# Flodar_Board_V1-2.net
KiCad netlist of a schematic drawn in EAGLE
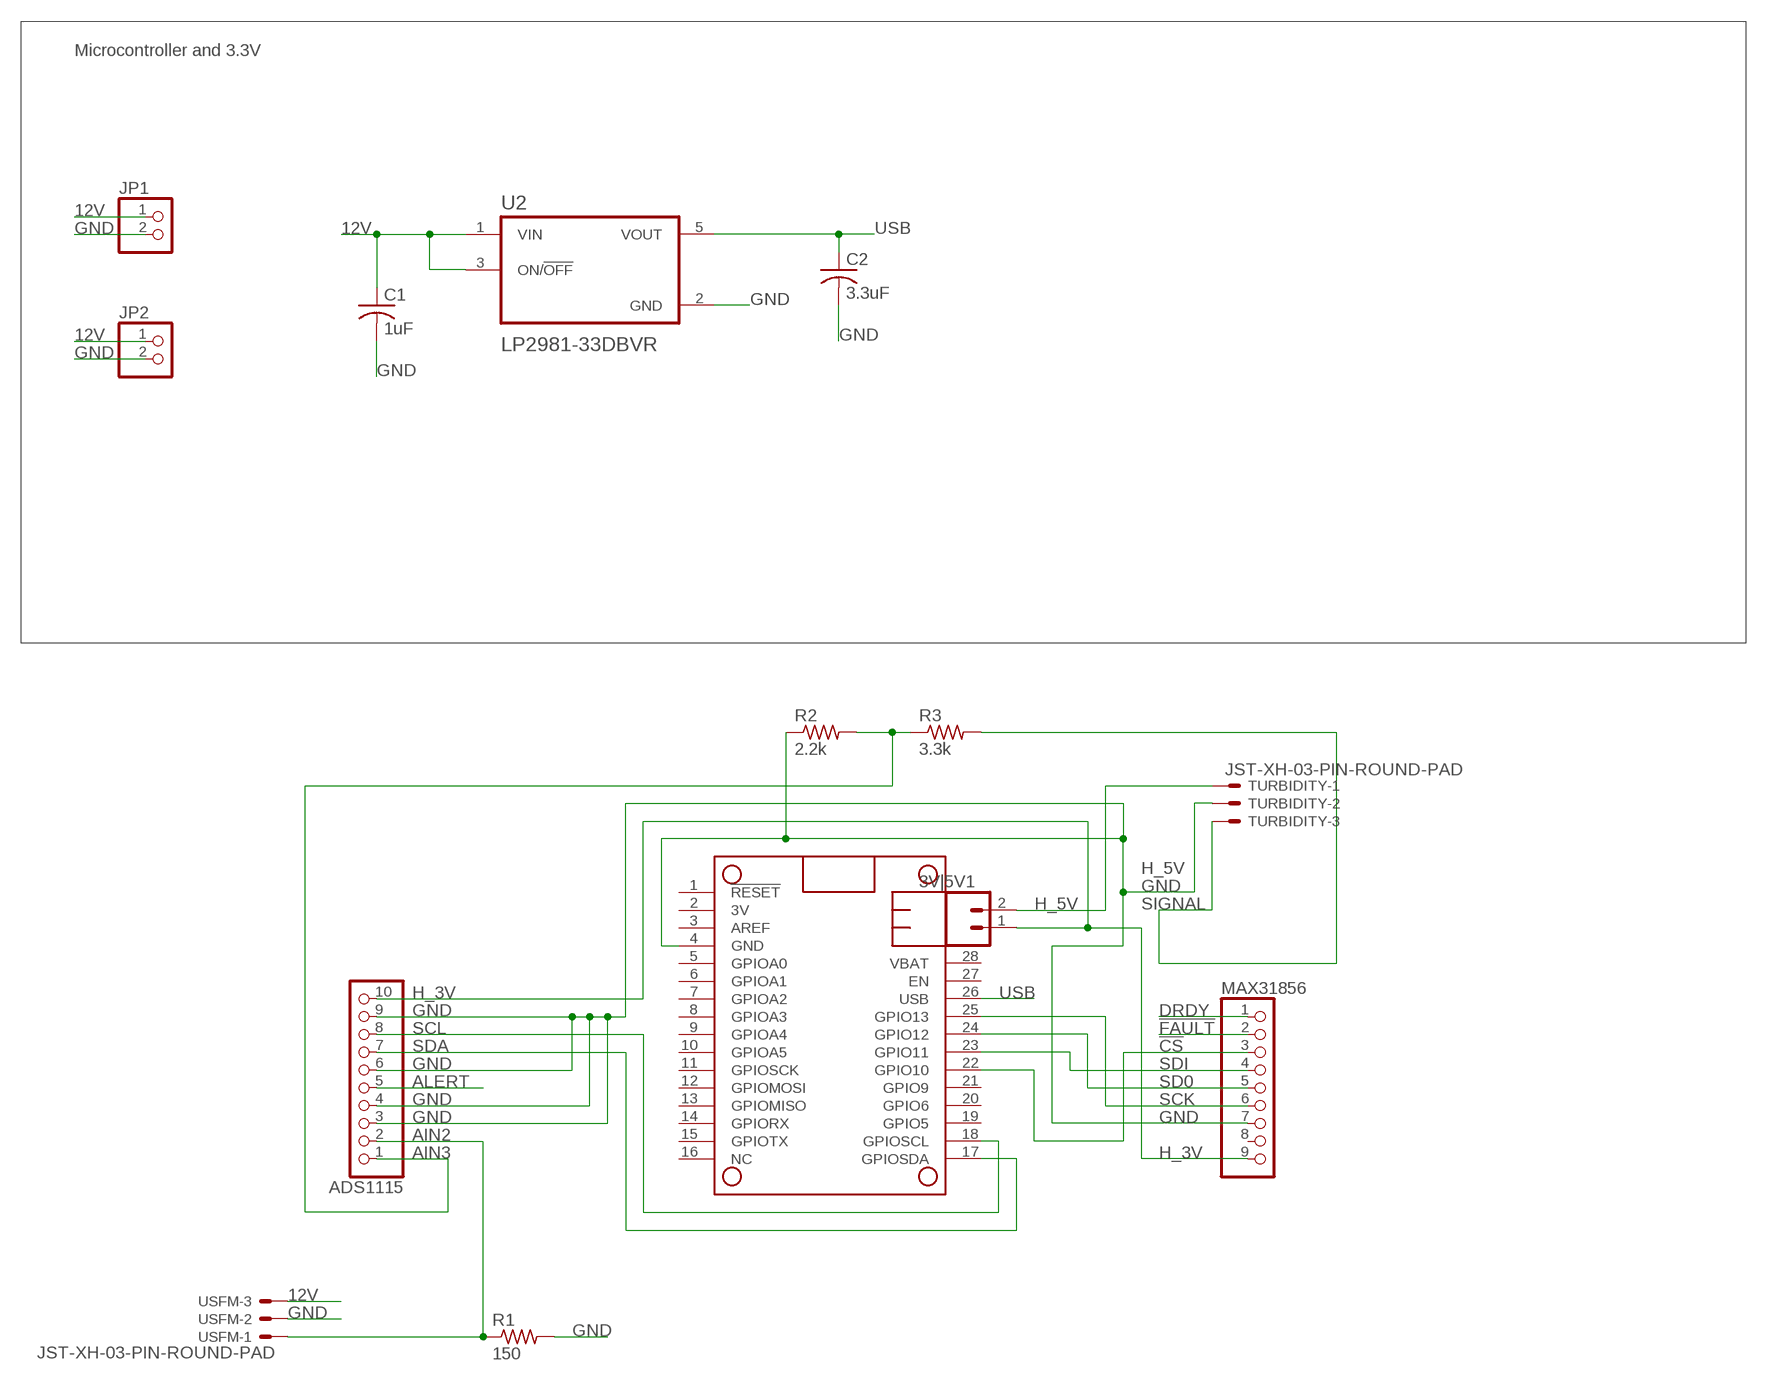
[diagram p0: schematic, sheet 1]

(export (version "E")
  (design (tool "Eeschema 10.0.6"))
  (components
    (comp (ref "3V|5V1")
      (value "CONN_021X02_NO_SILK")
      (footprint "eagle-import:1X02_NO_SILK")
      (libsource (lib "eagle-import") (part "CONN_021X02_NO_SILK"))
    )
    (comp (ref "ADS1115")
      (value "HEADER-1X1070MIL")
      (footprint "eagle-import:1X10_ROUND70")
      (libsource (lib "eagle-import") (part "HEADER-1X1070MIL"))
    )
    (comp (ref "C1")
      (value "1uF")
      (footprint "eagle-import:C1206")
      (libsource (lib "eagle-import") (part "C-USC1206"))
    )
    (comp (ref "C2")
      (value "3.3uF")
      (footprint "eagle-import:C1206")
      (libsource (lib "eagle-import") (part "C-USC1206"))
    )
    (comp (ref "JP1")
      (value "PINHD-1X2")
      (footprint "eagle-import:1X02")
      (libsource (lib "eagle-import") (part "PINHD-1X2"))
    )
    (comp (ref "JP2")
      (value "PINHD-1X2")
      (footprint "eagle-import:1X02")
      (libsource (lib "eagle-import") (part "PINHD-1X2"))
    )
    (comp (ref "MAX31856")
      (value "HEADER-1X970MIL")
      (footprint "eagle-import:1X09_ROUND_70")
      (libsource (lib "eagle-import") (part "HEADER-1X970MIL"))
    )
    (comp (ref "MS3")
      (value "FEATHERWING")
      (footprint "eagle-import:FEATHERWING")
      (libsource (lib "eagle-import") (part "FEATHERWING"))
    )
    (comp (ref "R1")
      (value "150")
      (footprint "eagle-import:R1206")
      (libsource (lib "eagle-import") (part "R-US_R1206"))
    )
    (comp (ref "R2")
      (value "2.2k")
      (footprint "eagle-import:R1206")
      (libsource (lib "eagle-import") (part "R-US_R1206"))
    )
    (comp (ref "R3")
      (value "3.3k")
      (footprint "eagle-import:R1206")
      (libsource (lib "eagle-import") (part "R-US_R1206"))
    )
    (comp (ref "TURBIDITY")
      (value "JST-XH-03-PIN-ROUND-PAD")
      (footprint "eagle-import:JST-XH-03-PACKAGE-ROUND-PAD")
      (libsource (lib "eagle-import") (part "JST-XH-03-PIN-ROUND-PAD"))
    )
    (comp (ref "U2")
      (value "LP2981-33DBVR")
      (footprint "eagle-import:SOT95P280X145-5N")
      (fields (field (name "MF") "Texas Instruments") (field (name "MP") "LP2981-50DBVR"))
      (libsource (lib "eagle-import") (part "LP2981-50DBVR"))
    )
    (comp (ref "USFM")
      (value "JST-XH-03-PIN-ROUND-PAD")
      (footprint "eagle-import:JST-XH-03-PACKAGE-ROUND-PAD")
      (libsource (lib "eagle-import") (part "JST-XH-03-PIN-ROUND-PAD"))
    )
  )
  (nets
    (net (code "1") (name "/3V") (class "Default")
      (node (ref "MS3") (pin "2") (pinfunction "3V_2") (pintype "power_in"))
    )
    (net (code "2") (name "/12V") (class "Default")
      (node (ref "C1") (pin "1") (pinfunction "1_1") (pintype "passive"))
      (node (ref "JP1") (pin "1") (pinfunction "1_1") (pintype "passive"))
      (node (ref "JP2") (pin "1") (pinfunction "1_1") (pintype "passive"))
      (node (ref "U2") (pin "1") (pinfunction "VIN_1") (pintype "input"))
      (node (ref "U2") (pin "3") (pinfunction "ON/~{OFF}_3") (pintype "bidirectional"))
      (node (ref "USFM") (pin "3") (pinfunction "S_3") (pintype "passive"))
    )
    (net (code "3") (name "/AIN2") (class "Default")
      (node (ref "ADS1115") (pin "2") (pinfunction "2_2") (pintype "passive"))
      (node (ref "R1") (pin "1") (pinfunction "1_1") (pintype "passive"))
      (node (ref "USFM") (pin "1") (pinfunction "S_1") (pintype "passive"))
    )
    (net (code "4") (name "/AIN3") (class "Default")
      (node (ref "ADS1115") (pin "1") (pinfunction "1_1") (pintype "passive"))
      (node (ref "R2") (pin "2") (pinfunction "2_2") (pintype "passive"))
      (node (ref "R3") (pin "1") (pinfunction "1_1") (pintype "passive"))
    )
    (net (code "5") (name "/ALERT") (class "Default")
      (node (ref "ADS1115") (pin "5") (pinfunction "5_5") (pintype "passive"))
    )
    (net (code "6") (name "/DRDY") (class "Default")
      (node (ref "MAX31856") (pin "1") (pinfunction "1_1") (pintype "passive"))
    )
    (net (code "7") (name "/GND") (class "Default")
      (node (ref "ADS1115") (pin "3") (pinfunction "3_3") (pintype "passive"))
      (node (ref "ADS1115") (pin "4") (pinfunction "4_4") (pintype "passive"))
      (node (ref "ADS1115") (pin "6") (pinfunction "6_6") (pintype "passive"))
      (node (ref "ADS1115") (pin "9") (pinfunction "9_9") (pintype "passive"))
      (node (ref "C1") (pin "2") (pinfunction "2_2") (pintype "passive"))
      (node (ref "C2") (pin "2") (pinfunction "2_2") (pintype "passive"))
      (node (ref "JP1") (pin "2") (pinfunction "2_2") (pintype "passive"))
      (node (ref "JP2") (pin "2") (pinfunction "2_2") (pintype "passive"))
      (node (ref "MAX31856") (pin "7") (pinfunction "7_7") (pintype "passive"))
      (node (ref "MS3") (pin "4") (pinfunction "GND_4") (pintype "power_in"))
      (node (ref "R1") (pin "2") (pinfunction "2_2") (pintype "passive"))
      (node (ref "R2") (pin "1") (pinfunction "1_1") (pintype "passive"))
      (node (ref "TURBIDITY") (pin "2") (pinfunction "S_2") (pintype "passive"))
      (node (ref "U2") (pin "2") (pinfunction "GND_2") (pintype "power_in"))
      (node (ref "USFM") (pin "2") (pinfunction "S_2") (pintype "passive"))
    )
    (net (code "8") (name "/H_3V") (class "Default")
      (node (ref "3V|5V1") (pin "1") (pinfunction "1_1") (pintype "passive"))
      (node (ref "ADS1115") (pin "10") (pinfunction "10_10") (pintype "passive"))
      (node (ref "MAX31856") (pin "9") (pinfunction "9_9") (pintype "passive"))
    )
    (net (code "9") (name "/H_5V") (class "Default")
      (node (ref "3V|5V1") (pin "2") (pinfunction "2_2") (pintype "passive"))
      (node (ref "TURBIDITY") (pin "1") (pinfunction "S_1") (pintype "passive"))
    )
    (net (code "10") (name "/SCK") (class "Default")
      (node (ref "MAX31856") (pin "6") (pinfunction "6_6") (pintype "passive"))
      (node (ref "MS3") (pin "25") (pinfunction "GPIO13_25") (pintype "bidirectional"))
    )
    (net (code "11") (name "/SCL") (class "Default")
      (node (ref "ADS1115") (pin "8") (pinfunction "8_8") (pintype "passive"))
      (node (ref "MS3") (pin "18") (pinfunction "GPIOSCL_18") (pintype "bidirectional"))
    )
    (net (code "12") (name "/SD0") (class "Default")
      (node (ref "MAX31856") (pin "5") (pinfunction "5_5") (pintype "passive"))
      (node (ref "MS3") (pin "24") (pinfunction "GPIO12_24") (pintype "bidirectional"))
    )
    (net (code "13") (name "/SDA") (class "Default")
      (node (ref "ADS1115") (pin "7") (pinfunction "7_7") (pintype "passive"))
      (node (ref "MS3") (pin "17") (pinfunction "GPIOSDA_17") (pintype "bidirectional"))
    )
    (net (code "14") (name "/SDI") (class "Default")
      (node (ref "MAX31856") (pin "4") (pinfunction "4_4") (pintype "passive"))
      (node (ref "MS3") (pin "23") (pinfunction "GPIO11_23") (pintype "bidirectional"))
    )
    (net (code "15") (name "/SIGNAL") (class "Default")
      (node (ref "R3") (pin "2") (pinfunction "2_2") (pintype "passive"))
      (node (ref "TURBIDITY") (pin "3") (pinfunction "S_3") (pintype "passive"))
    )
    (net (code "16") (name "/USB") (class "Default")
      (node (ref "C2") (pin "1") (pinfunction "1_1") (pintype "passive"))
      (node (ref "MS3") (pin "26") (pinfunction "USB_26") (pintype "power_in"))
      (node (ref "U2") (pin "5") (pinfunction "VOUT_5") (pintype "output"))
    )
    (net (code "17") (name "/VBAT") (class "Default")
      (node (ref "MS3") (pin "28") (pinfunction "VBAT_28") (pintype "power_in"))
    )
    (net (code "18") (name "/~{CS}") (class "Default")
      (node (ref "MAX31856") (pin "3") (pinfunction "3_3") (pintype "passive"))
      (node (ref "MS3") (pin "22") (pinfunction "GPIO10_22") (pintype "bidirectional"))
    )
    (net (code "19") (name "/~{FAULT}") (class "Default")
      (node (ref "MAX31856") (pin "2") (pinfunction "2_2") (pintype "passive"))
    )
    (net (code "20") (name "unconnected-(MAX31856-Pad8)") (class "Default")
      (node (ref "MAX31856") (pin "8") (pinfunction "8_8") (pintype "passive"))
    )
    (net (code "21") (name "unconnected-(MS3-AREF-Pad3)") (class "Default")
      (node (ref "MS3") (pin "3") (pinfunction "AREF_3") (pintype "passive"))
    )
    (net (code "22") (name "unconnected-(MS3-EN-Pad27)") (class "Default")
      (node (ref "MS3") (pin "27") (pinfunction "EN_27") (pintype "passive"))
    )
    (net (code "23") (name "unconnected-(MS3-GPIO5-Pad19)") (class "Default")
      (node (ref "MS3") (pin "19") (pinfunction "GPIO5_19") (pintype "bidirectional"))
    )
    (net (code "24") (name "unconnected-(MS3-GPIO6-Pad20)") (class "Default")
      (node (ref "MS3") (pin "20") (pinfunction "GPIO6_20") (pintype "bidirectional"))
    )
    (net (code "25") (name "unconnected-(MS3-GPIO9-Pad21)") (class "Default")
      (node (ref "MS3") (pin "21") (pinfunction "GPIO9_21") (pintype "bidirectional"))
    )
    (net (code "26") (name "unconnected-(MS3-GPIOA0-Pad5)") (class "Default")
      (node (ref "MS3") (pin "5") (pinfunction "GPIOA0_5") (pintype "bidirectional"))
    )
    (net (code "27") (name "unconnected-(MS3-GPIOA1-Pad6)") (class "Default")
      (node (ref "MS3") (pin "6") (pinfunction "GPIOA1_6") (pintype "bidirectional"))
    )
    (net (code "28") (name "unconnected-(MS3-GPIOA2-Pad7)") (class "Default")
      (node (ref "MS3") (pin "7") (pinfunction "GPIOA2_7") (pintype "bidirectional"))
    )
    (net (code "29") (name "unconnected-(MS3-GPIOA3-Pad8)") (class "Default")
      (node (ref "MS3") (pin "8") (pinfunction "GPIOA3_8") (pintype "bidirectional"))
    )
    (net (code "30") (name "unconnected-(MS3-GPIOA4-Pad9)") (class "Default")
      (node (ref "MS3") (pin "9") (pinfunction "GPIOA4_9") (pintype "bidirectional"))
    )
    (net (code "31") (name "unconnected-(MS3-GPIOA5-Pad10)") (class "Default")
      (node (ref "MS3") (pin "10") (pinfunction "GPIOA5_10") (pintype "bidirectional"))
    )
    (net (code "32") (name "unconnected-(MS3-GPIOMISO-Pad13)") (class "Default")
      (node (ref "MS3") (pin "13") (pinfunction "GPIOMISO_13") (pintype "bidirectional"))
    )
    (net (code "33") (name "unconnected-(MS3-GPIOMOSI-Pad12)") (class "Default")
      (node (ref "MS3") (pin "12") (pinfunction "GPIOMOSI_12") (pintype "bidirectional"))
    )
    (net (code "34") (name "unconnected-(MS3-GPIORX-Pad14)") (class "Default")
      (node (ref "MS3") (pin "14") (pinfunction "GPIORX_14") (pintype "bidirectional"))
    )
    (net (code "35") (name "unconnected-(MS3-GPIOSCK-Pad11)") (class "Default")
      (node (ref "MS3") (pin "11") (pinfunction "GPIOSCK_11") (pintype "bidirectional"))
    )
    (net (code "36") (name "unconnected-(MS3-GPIOTX-Pad15)") (class "Default")
      (node (ref "MS3") (pin "15") (pinfunction "GPIOTX_15") (pintype "bidirectional"))
    )
    (net (code "37") (name "unconnected-(MS3-NC-Pad16)") (class "Default")
      (node (ref "MS3") (pin "16") (pinfunction "NC_16") (pintype "passive"))
    )
    (net (code "38") (name "unconnected-(MS3-~{RESET}-Pad1)") (class "Default")
      (node (ref "MS3") (pin "1") (pinfunction "~{RESET}_1") (pintype "input"))
    )
  )
)
